# Alimenta_o.net
KiCad netlist of a schematic drawn in Altium Designer
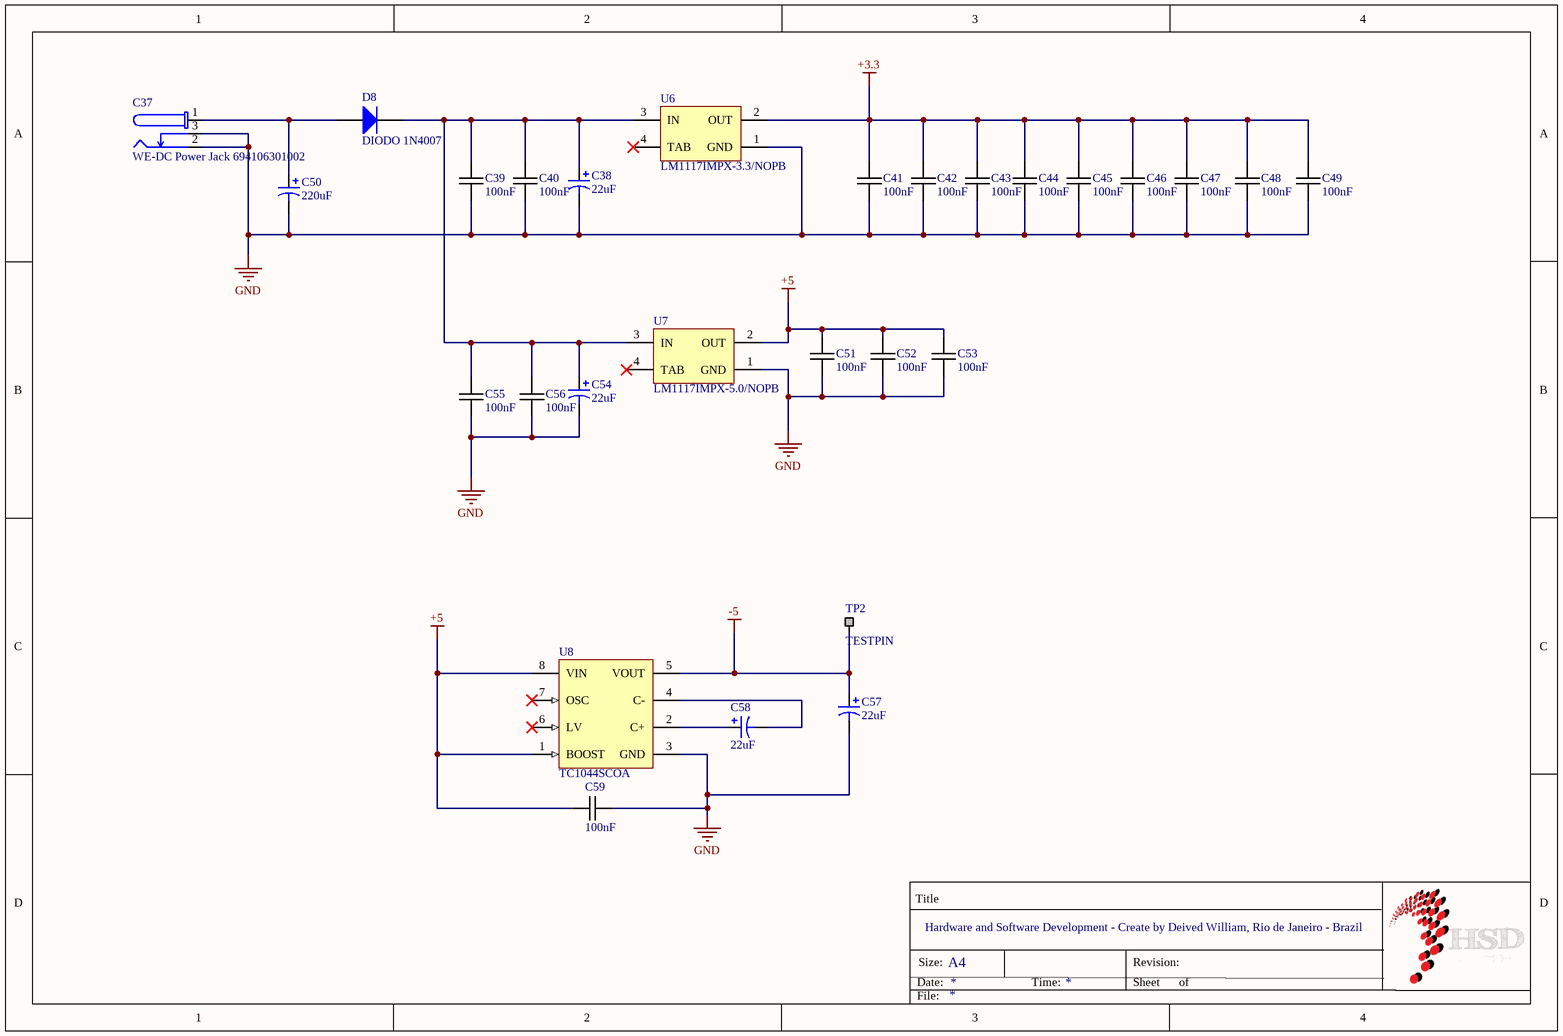
[diagram p0: Alimentação.SchDoc]

(export (version "E")
  (design (tool "Eeschema 10.0.6"))
  (components
    (comp (ref "C37")
      (value "WE-DC Power Jack 694106301002")
      (footprint "694106301002")
      (description "WR-DC_DC Power Jack_Right Angled_THT")
      (fields
        (field (name "MANUFACTURER") "Würth Elektronik eiSos GmbH")
        (field (name "PARTNO") "694106301002")
        (field (name "CREATED BY") "Karrer Zheng")
      )
      (libsource (lib "DC_Power_Jack_rev15b") (part "WE-DC Power Jack 694106301002"))
    )
    (comp (ref "C38")
      (value "22uF")
      (footprint "D")
      (fields (field (name "PUBLISHER") "Altium Limited"))
      (libsource (lib "Vishay Sprague Tantalum Chip Capacitor") (part "CC106D004M"))
    )
    (comp (ref "C39")
      (value "100nF")
      (footprint "0603C-GENERIC")
      (description "CAPACITOR 0603 CERAMIC")
      (fields (field (name "TOLERANCE") "±10%") (field (name "MANUFACTURER PART NUMBER") "C1608X7R1H103K"))
      (libsource (lib "vh_altium_library") (part "0603C-100NF-50V-X7R-TDK"))
    )
    (comp (ref "C40")
      (value "100nF")
      (footprint "0603C-GENERIC")
      (description "CAPACITOR 0603 CERAMIC")
      (fields (field (name "TOLERANCE") "±10%") (field (name "MANUFACTURER PART NUMBER") "C1608X7R1H103K"))
      (libsource (lib "vh_altium_library") (part "0603C-100NF-50V-X7R-TDK"))
    )
    (comp (ref "C41")
      (value "100nF")
      (footprint "0603C-GENERIC")
      (description "CAPACITOR 0603 CERAMIC")
      (fields (field (name "TOLERANCE") "±10%") (field (name "MANUFACTURER PART NUMBER") "C1608X7R1H103K"))
      (libsource (lib "vh_altium_library") (part "0603C-100NF-50V-X7R-TDK"))
    )
    (comp (ref "C42")
      (value "100nF")
      (footprint "0603C-GENERIC")
      (description "CAPACITOR 0603 CERAMIC")
      (fields (field (name "TOLERANCE") "±10%") (field (name "MANUFACTURER PART NUMBER") "C1608X7R1H103K"))
      (libsource (lib "vh_altium_library") (part "0603C-100NF-50V-X7R-TDK"))
    )
    (comp (ref "C43")
      (value "100nF")
      (footprint "0603C-GENERIC")
      (description "CAPACITOR 0603 CERAMIC")
      (fields (field (name "TOLERANCE") "±10%") (field (name "MANUFACTURER PART NUMBER") "C1608X7R1H103K"))
      (libsource (lib "vh_altium_library") (part "0603C-100NF-50V-X7R-TDK"))
    )
    (comp (ref "C44")
      (value "100nF")
      (footprint "0603C-GENERIC")
      (description "CAPACITOR 0603 CERAMIC")
      (fields (field (name "TOLERANCE") "±10%") (field (name "MANUFACTURER PART NUMBER") "C1608X7R1H103K"))
      (libsource (lib "vh_altium_library") (part "0603C-100NF-50V-X7R-TDK"))
    )
    (comp (ref "C45")
      (value "100nF")
      (footprint "0603C-GENERIC")
      (description "CAPACITOR 0603 CERAMIC")
      (fields (field (name "TOLERANCE") "±10%") (field (name "MANUFACTURER PART NUMBER") "C1608X7R1H103K"))
      (libsource (lib "vh_altium_library") (part "0603C-100NF-50V-X7R-TDK"))
    )
    (comp (ref "C46")
      (value "100nF")
      (footprint "0603C-GENERIC")
      (description "CAPACITOR 0603 CERAMIC")
      (fields (field (name "TOLERANCE") "±10%") (field (name "MANUFACTURER PART NUMBER") "C1608X7R1H103K"))
      (libsource (lib "vh_altium_library") (part "0603C-100NF-50V-X7R-TDK"))
    )
    (comp (ref "C47")
      (value "100nF")
      (footprint "0603C-GENERIC")
      (description "CAPACITOR 0603 CERAMIC")
      (fields (field (name "TOLERANCE") "±10%") (field (name "MANUFACTURER PART NUMBER") "C1608X7R1H103K"))
      (libsource (lib "vh_altium_library") (part "0603C-100NF-50V-X7R-TDK"))
    )
    (comp (ref "C48")
      (value "100nF")
      (footprint "0603C-GENERIC")
      (description "CAPACITOR 0603 CERAMIC")
      (fields (field (name "TOLERANCE") "±10%") (field (name "MANUFACTURER PART NUMBER") "C1608X7R1H103K"))
      (libsource (lib "vh_altium_library") (part "0603C-100NF-50V-X7R-TDK"))
    )
    (comp (ref "C49")
      (value "100nF")
      (footprint "0603C-GENERIC")
      (description "CAPACITOR 0603 CERAMIC")
      (fields (field (name "TOLERANCE") "±10%") (field (name "MANUFACTURER PART NUMBER") "C1608X7R1H103K"))
      (libsource (lib "vh_altium_library") (part "0603C-100NF-50V-X7R-TDK"))
    )
    (comp (ref "C50")
      (value "220uF")
      (footprint "D")
      (fields (field (name "PUBLISHER") "Altium Limited"))
      (libsource (lib "Vishay Sprague Tantalum Chip Capacitor") (part "CC106D004M"))
    )
    (comp (ref "C51")
      (value "100nF")
      (footprint "0603C-GENERIC")
      (description "CAPACITOR 0603 CERAMIC")
      (fields (field (name "TOLERANCE") "±10%") (field (name "MANUFACTURER PART NUMBER") "C1608X7R1H103K"))
      (libsource (lib "vh_altium_library") (part "0603C-100NF-50V-X7R-TDK"))
    )
    (comp (ref "C52")
      (value "100nF")
      (footprint "0603C-GENERIC")
      (description "CAPACITOR 0603 CERAMIC")
      (fields (field (name "TOLERANCE") "±10%") (field (name "MANUFACTURER PART NUMBER") "C1608X7R1H103K"))
      (libsource (lib "vh_altium_library") (part "0603C-100NF-50V-X7R-TDK"))
    )
    (comp (ref "C53")
      (value "100nF")
      (footprint "0603C-GENERIC")
      (description "CAPACITOR 0603 CERAMIC")
      (fields (field (name "TOLERANCE") "±10%") (field (name "MANUFACTURER PART NUMBER") "C1608X7R1H103K"))
      (libsource (lib "vh_altium_library") (part "0603C-100NF-50V-X7R-TDK"))
    )
    (comp (ref "C54")
      (value "22uF")
      (footprint "D")
      (fields (field (name "PUBLISHER") "Altium Limited"))
      (libsource (lib "Vishay Sprague Tantalum Chip Capacitor") (part "CC106D004M"))
    )
    (comp (ref "C55")
      (value "100nF")
      (footprint "0603C-GENERIC")
      (description "CAPACITOR 0603 CERAMIC")
      (fields (field (name "TOLERANCE") "±10%") (field (name "MANUFACTURER PART NUMBER") "C1608X7R1H103K"))
      (libsource (lib "vh_altium_library") (part "0603C-100NF-50V-X7R-TDK"))
    )
    (comp (ref "C56")
      (value "100nF")
      (footprint "0603C-GENERIC")
      (description "CAPACITOR 0603 CERAMIC")
      (fields (field (name "TOLERANCE") "±10%") (field (name "MANUFACTURER PART NUMBER") "C1608X7R1H103K"))
      (libsource (lib "vh_altium_library") (part "0603C-100NF-50V-X7R-TDK"))
    )
    (comp (ref "C57")
      (value "22uF")
      (footprint "D")
      (fields (field (name "PUBLISHER") "Altium Limited"))
      (libsource (lib "Vishay Sprague Tantalum Chip Capacitor") (part "CC106D004M"))
    )
    (comp (ref "C58")
      (value "22uF")
      (footprint "D")
      (fields (field (name "PUBLISHER") "Altium Limited"))
      (libsource (lib "Vishay Sprague Tantalum Chip Capacitor") (part "CC106D004M"))
    )
    (comp (ref "C59")
      (value "100nF")
      (footprint "0603C-GENERIC")
      (description "CAPACITOR 0603 CERAMIC")
      (fields (field (name "TOLERANCE") "±10%") (field (name "MANUFACTURER PART NUMBER") "C1608X7R1H103K"))
      (libsource (lib "vh_altium_library") (part "0603C-100NF-50V-X7R-TDK"))
    )
    (comp (ref "D8")
      (value "DIODO 1N4007")
      (footprint "DO-41")
      (description "1 Amp General Purpose Rectifier")
      (fields (field (name "PUBLISHER") "Altium Limited"))
      (libsource (lib "Hardware_DF_Controlador_Temperatura") (part "DIODO 1N4007"))
    )
    (comp (ref "TP2")
      (value "TESTPIN")
      (footprint "TESTPIN")
      (description "TESTPIN SINGLE PIN HEADER")
      (libsource (lib "vh_altium_library") (part "TESTPIN"))
    )
    (comp (ref "U6")
      (value "LM1117IMPX-3.3/NOPB")
      (footprint "MP04A_N")
      (description "800mA Low-Dropout Linear Regulator, 4-pin SOT-223, Pb-Free")
      (fields
        (field (name "MANUFACTURER") "National Semiconductor")
        (field (name "PUBLISHER") "Altium Limited")
      )
      (libsource (lib "NSC LDO") (part "LM1117IMPX-3.3/NOPB"))
    )
    (comp (ref "U7")
      (value "LM1117IMPX-5.0/NOPB")
      (footprint "MP04A_N")
      (description "800mA Low-Dropout Linear Regulator, 4-pin SOT-223, Pb-Free")
      (fields
        (field (name "MANUFACTURER") "National Semiconductor")
        (field (name "PUBLISHER") "Altium Limited")
      )
      (libsource (lib "NSC LDO") (part "LM1117IMPX-5.0/NOPB"))
    )
    (comp (ref "U8")
      (value "TC1044SCOA")
      (footprint "SOIC-OA8_N")
      (description "Charge Pump DC-TO-DC Voltage Converter, 8-Pin SOIC 150mil, Commercial Temperature")
      (fields (field (name "PUBLISHER") "Altium Limited"))
      (libsource (lib "Microchip Power Mgt Charge Pump") (part "TC1044SCOA"))
    )
  )
  (nets
    (net (code "1") (name "+3.3") (class "Default")
      (node (ref "C41") (pin "1") (pintype "passive"))
      (node (ref "C42") (pin "1") (pintype "passive"))
      (node (ref "C43") (pin "1") (pintype "passive"))
      (node (ref "C44") (pin "1") (pintype "passive"))
      (node (ref "C45") (pin "1") (pintype "passive"))
      (node (ref "C46") (pin "1") (pintype "passive"))
      (node (ref "C47") (pin "1") (pintype "passive"))
      (node (ref "C48") (pin "1") (pintype "passive"))
      (node (ref "C49") (pin "1") (pintype "passive"))
      (node (ref "U6") (pin "2") (pinfunction "OUT_2") (pintype "power_in"))
    )
    (net (code "2") (name "+5") (class "Default")
      (node (ref "C51") (pin "1") (pintype "passive"))
      (node (ref "C52") (pin "1") (pintype "passive"))
      (node (ref "C53") (pin "1") (pintype "passive"))
      (node (ref "C59") (pin "1") (pintype "passive"))
      (node (ref "U7") (pin "2") (pinfunction "OUT_2") (pintype "power_in"))
      (node (ref "U8") (pin "1") (pinfunction "BOOST_1") (pintype "input"))
      (node (ref "U8") (pin "8") (pinfunction "VIN_8") (pintype "power_in"))
    )
    (net (code "3") (name "-5") (class "Default")
      (node (ref "C57") (pin "1") (pinfunction "1_1") (pintype "passive"))
      (node (ref "TP2") (pin "1") (pinfunction "1_1") (pintype "passive"))
      (node (ref "U8") (pin "5") (pinfunction "VOUT_5") (pintype "power_in"))
    )
    (net (code "4") (name "GND") (class "Default")
      (node (ref "C37") (pin "2") (pinfunction "2_2") (pintype "power_in"))
      (node (ref "C37") (pin "3") (pinfunction "3_3") (pintype "power_in"))
      (node (ref "C38") (pin "2") (pinfunction "2_2") (pintype "passive"))
      (node (ref "C39") (pin "2") (pintype "passive"))
      (node (ref "C40") (pin "2") (pintype "passive"))
      (node (ref "C41") (pin "2") (pintype "passive"))
      (node (ref "C42") (pin "2") (pintype "passive"))
      (node (ref "C43") (pin "2") (pintype "passive"))
      (node (ref "C44") (pin "2") (pintype "passive"))
      (node (ref "C45") (pin "2") (pintype "passive"))
      (node (ref "C46") (pin "2") (pintype "passive"))
      (node (ref "C47") (pin "2") (pintype "passive"))
      (node (ref "C48") (pin "2") (pintype "passive"))
      (node (ref "C49") (pin "2") (pintype "passive"))
      (node (ref "C50") (pin "2") (pinfunction "2_2") (pintype "passive"))
      (node (ref "C51") (pin "2") (pintype "passive"))
      (node (ref "C52") (pin "2") (pintype "passive"))
      (node (ref "C53") (pin "2") (pintype "passive"))
      (node (ref "C54") (pin "2") (pinfunction "2_2") (pintype "passive"))
      (node (ref "C55") (pin "2") (pintype "passive"))
      (node (ref "C56") (pin "2") (pintype "passive"))
      (node (ref "C57") (pin "2") (pinfunction "2_2") (pintype "passive"))
      (node (ref "C59") (pin "2") (pintype "passive"))
      (node (ref "U6") (pin "1") (pinfunction "GND_1") (pintype "power_in"))
      (node (ref "U7") (pin "1") (pinfunction "GND_1") (pintype "power_in"))
      (node (ref "U8") (pin "3") (pinfunction "GND_3") (pintype "power_in"))
    )
    (net (code "5") (name "Net-(D8-A)") (class "Default")
      (node (ref "C37") (pin "1") (pinfunction "1_1") (pintype "power_in"))
      (node (ref "C50") (pin "1") (pinfunction "1_1") (pintype "passive"))
      (node (ref "D8") (pin "1") (pinfunction "A_1") (pintype "passive"))
    )
    (net (code "6") (name "Net-(D8-K)") (class "Default")
      (node (ref "C38") (pin "1") (pinfunction "1_1") (pintype "passive"))
      (node (ref "C39") (pin "1") (pintype "passive"))
      (node (ref "C40") (pin "1") (pintype "passive"))
      (node (ref "C54") (pin "1") (pinfunction "1_1") (pintype "passive"))
      (node (ref "C55") (pin "1") (pintype "passive"))
      (node (ref "C56") (pin "1") (pintype "passive"))
      (node (ref "D8") (pin "2") (pinfunction "K_2") (pintype "passive"))
      (node (ref "U6") (pin "3") (pinfunction "IN_3") (pintype "power_in"))
      (node (ref "U7") (pin "3") (pinfunction "IN_3") (pintype "power_in"))
    )
    (net (code "7") (name "Net-(U8-C+)") (class "Default")
      (node (ref "C58") (pin "1") (pinfunction "1_1") (pintype "passive"))
      (node (ref "U8") (pin "2") (pinfunction "C+_2") (pintype "passive"))
    )
    (net (code "8") (name "Net-(U8-C-)") (class "Default")
      (node (ref "C58") (pin "2") (pinfunction "2_2") (pintype "passive"))
      (node (ref "U8") (pin "4") (pinfunction "C-_4") (pintype "passive"))
    )
    (net (code "9") (name "unconnected-(U6-TAB-Pad4)") (class "Default")
      (node (ref "U6") (pin "4") (pinfunction "TAB_4") (pintype "power_in+no_connect"))
    )
    (net (code "10") (name "unconnected-(U7-TAB-Pad4)") (class "Default")
      (node (ref "U7") (pin "4") (pinfunction "TAB_4") (pintype "power_in+no_connect"))
    )
    (net (code "11") (name "unconnected-(U8-LV-Pad6)") (class "Default")
      (node (ref "U8") (pin "6") (pinfunction "LV_6") (pintype "input+no_connect"))
    )
    (net (code "12") (name "unconnected-(U8-OSC-Pad7)") (class "Default")
      (node (ref "U8") (pin "7") (pinfunction "OSC_7") (pintype "input+no_connect"))
    )
  )
)
